# Sheet2.net
KiCad netlist of a schematic drawn in Altium Designer
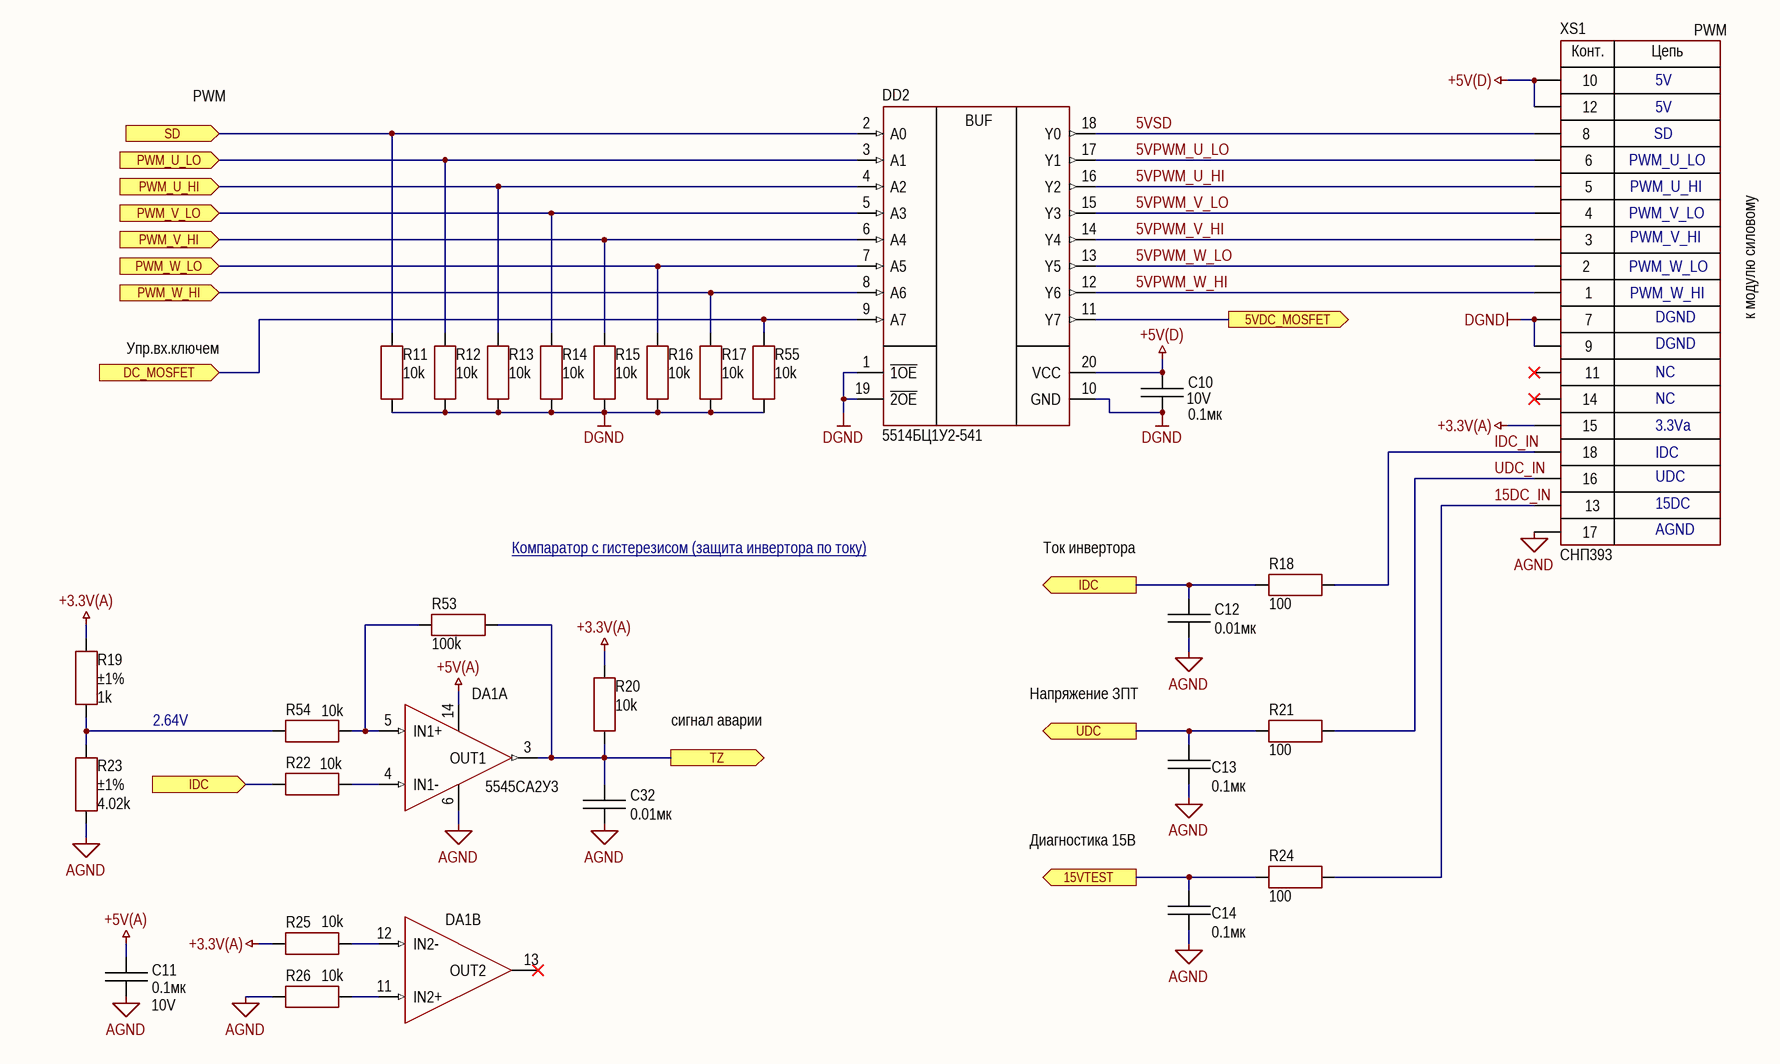
[diagram p0: Sheet2.SchDoc]

(export (version "E")
  (design (tool "Eeschema 10.0.6"))
  (components
    (comp (ref "C10")
      (value "0.1мк")
      (footprint "StandardCase:CAP: 0603P")
      (fields
        (field (name "MANUFACTURER") "Гириконд")
        (field (name "PARTNUMBER") "К10-79-10В-0,1 мкФ +80-20% H90")
        (field (name "VALUEMANUFACTURERPARTNUMBER") "Ceramic capacitor, 0.1мк, H90, +80-20%, 10V, 0603, -55...+125°C")
        (field (name "VOLTAGE") "10V")
      )
      (libsource (lib "Capacitor") (part "Ceramic_0603"))
    )
    (comp (ref "C11")
      (value "0.1мк")
      (footprint "StandardCase:CAP: 0603P")
      (fields
        (field (name "MANUFACTURER") "Гириконд")
        (field (name "PARTNUMBER") "К10-79-10В-0,1 мкФ +80-20% H90")
        (field (name "VALUEMANUFACTURERPARTNUMBER") "Ceramic capacitor, 0.1мк, H90, +80-20%, 10V, 0603, -55...+125°C")
        (field (name "VOLTAGE") "10V")
      )
      (libsource (lib "Capacitor") (part "Ceramic_0603"))
    )
    (comp (ref "C12")
      (value "0.01мк")
      (footprint "StandardCase:CAP: 0603P")
      (fields
        (field (name "MANUFACTURER") "Монолит")
        (field (name "PARTNUMBER") "К10-84в-1608М-50В-0.01мк ±20%-Н20-N-A")
        (field (name "VALUEMANUFACTURERPARTNUMBER") "Ceramic capacitor, 0.01мк, H20, ±20%, 50V, 0603, -55...+125°C")
      )
      (libsource (lib "Capacitor") (part "Ceramic_0603"))
    )
    (comp (ref "C13")
      (value "0.1мк")
      (footprint "StandardCase:CAP: 0603P")
      (fields
        (field (name "MANUFACTURER") "Гириконд")
        (field (name "PARTNUMBER") "К10-79-10В-0,1 мкФ +80-20% H90")
        (field (name "VALUEMANUFACTURERPARTNUMBER") "Ceramic capacitor, 0.1мк, H90, +80-20%, 10V, 0603, -55...+125°C")
      )
      (libsource (lib "Capacitor") (part "Ceramic_0603"))
    )
    (comp (ref "C14")
      (value "0.1мк")
      (footprint "StandardCase:CAP: 0603P")
      (fields
        (field (name "MANUFACTURER") "Гириконд")
        (field (name "PARTNUMBER") "К10-79-10В-0,1 мкФ +80-20% H90")
        (field (name "VALUEMANUFACTURERPARTNUMBER") "Ceramic capacitor, 0.1мк, H90, +80-20%, 10V, 0603, -55...+125°C")
      )
      (libsource (lib "Capacitor") (part "Ceramic_0603"))
    )
    (comp (ref "C32")
      (value "0.01мк")
      (footprint "StandardCase:CAP: 0603P")
      (fields
        (field (name "MANUFACTURER") "Монолит")
        (field (name "PARTNUMBER") "К10-84в-1608М-50В-0.01мк ±20%-Н20-N-A")
        (field (name "VALUEMANUFACTURERPARTNUMBER") "Ceramic capacitor, 0.01мк, H20, ±20%, 50V, 0603, -55...+125°C")
      )
      (libsource (lib "Capacitor") (part "Ceramic_0603"))
    )
    (comp (ref "DA1")
      (value "~")
      (footprint "StandardCase:16-Н04.16-1B")
      (description "Comparator USSR")
      (fields
        (field (name "MANUFACTURER") "НПП ВОСТОК")
        (field (name "VALUEMANUFACTURERPARTNUMBER") "IC comparator, Open Drain, от ± 1,5В до ± 16,5В, -60...+125°C, Н04.16-1В")
        (field (name "PARTNUMBER") "5545СА2У3")
      )
      (libsource (lib "IC. Comparator") (part "5545СА2У3"))
    )
    (comp (ref "DD2")
      (value "~")
      (footprint "StandardCase:20-QLCC (5121.20-A)")
      (description "USSR Buffer QFN")
      (fields
        (field (name "MANUFACTURER") "Анстрем")
        (field (name "VALUEMANUFACTURERPARTNUMBER") "8 канальный буфер, 4.5..5.5V, -60...+125°C, 5121.20-A")
        (field (name "PARTNUMBER") "5514БЦ1У2-541")
      )
      (libsource (lib "IC. Logic") (part "5514БЦ1У2-541"))
    )
    (comp (ref "R11")
      (value "10k")
      (footprint "RES: 0603P")
      (fields
        (field (name "MANUFACTURER") "ОАО Ресурс")
        (field (name "PARTNUMBER") "Р1-12-0,1ум.-10~кОм ±5%-М ШКАБ.434110.002 ТУ")
        (field (name "VALUEMANUFACTURERPARTNUMBER") "Resistor film, 10k, ±5%, 0603, 0.1W, -55...+125°C")
      )
      (libsource (lib "") (part "Resistor_0603_1"))
    )
    (comp (ref "R12")
      (value "10k")
      (footprint "RES: 0603P")
      (fields
        (field (name "MANUFACTURER") "ОАО Ресурс")
        (field (name "PARTNUMBER") "Р1-12-0,1ум.-10~кОм ±5%-М ШКАБ.434110.002 ТУ")
        (field (name "VALUEMANUFACTURERPARTNUMBER") "Resistor film, 10k, ±5%, 0603, 0.1W, -55...+125°C")
      )
      (libsource (lib "") (part "Resistor_0603_1"))
    )
    (comp (ref "R13")
      (value "10k")
      (footprint "RES: 0603P")
      (fields
        (field (name "MANUFACTURER") "ОАО Ресурс")
        (field (name "PARTNUMBER") "Р1-12-0,1ум.-10~кОм ±5%-М ШКАБ.434110.002 ТУ")
        (field (name "VALUEMANUFACTURERPARTNUMBER") "Resistor film, 10k, ±5%, 0603, 0.1W, -55...+125°C")
      )
      (libsource (lib "") (part "Resistor_0603_1"))
    )
    (comp (ref "R14")
      (value "10k")
      (footprint "RES: 0603P")
      (fields
        (field (name "MANUFACTURER") "ОАО Ресурс")
        (field (name "PARTNUMBER") "Р1-12-0,1ум.-10~кОм ±5%-М ШКАБ.434110.002 ТУ")
        (field (name "VALUEMANUFACTURERPARTNUMBER") "Resistor film, 10k, ±5%, 0603, 0.1W, -55...+125°C")
      )
      (libsource (lib "") (part "Resistor_0603_1"))
    )
    (comp (ref "R15")
      (value "10k")
      (footprint "RES: 0603P")
      (fields
        (field (name "MANUFACTURER") "ОАО Ресурс")
        (field (name "PARTNUMBER") "Р1-12-0,1ум.-10~кОм ±5%-М ШКАБ.434110.002 ТУ")
        (field (name "VALUEMANUFACTURERPARTNUMBER") "Resistor film, 10k, ±5%, 0603, 0.1W, -55...+125°C")
      )
      (libsource (lib "") (part "Resistor_0603_1"))
    )
    (comp (ref "R16")
      (value "10k")
      (footprint "RES: 0603P")
      (fields
        (field (name "MANUFACTURER") "ОАО Ресурс")
        (field (name "PARTNUMBER") "Р1-12-0,1ум.-10~кОм ±5%-М ШКАБ.434110.002 ТУ")
        (field (name "VALUEMANUFACTURERPARTNUMBER") "Resistor film, 10k, ±5%, 0603, 0.1W, -55...+125°C")
      )
      (libsource (lib "") (part "Resistor_0603_1"))
    )
    (comp (ref "R17")
      (value "10k")
      (footprint "RES: 0603P")
      (fields
        (field (name "MANUFACTURER") "ОАО Ресурс")
        (field (name "PARTNUMBER") "Р1-12-0,1ум.-10~кОм ±5%-М ШКАБ.434110.002 ТУ")
        (field (name "VALUEMANUFACTURERPARTNUMBER") "Resistor film, 10k, ±5%, 0603, 0.1W, -55...+125°C")
      )
      (libsource (lib "") (part "Resistor_0603_1"))
    )
    (comp (ref "R18")
      (value "100")
      (footprint "RES: 0603P")
      (fields
        (field (name "MANUFACTURER") "ОАО Ресурс")
        (field (name "PARTNUMBER") "Р1-12-0,1ум.-100~Ом ±5%-М ШКАБ.434110.002 ТУ")
        (field (name "VALUEMANUFACTURERPARTNUMBER") "Resistor film, 100, ±5%, 0603, 0.1W, -55...+125°C")
      )
      (libsource (lib "") (part "Resistor_0603_1"))
    )
    (comp (ref "R19")
      (value "1k")
      (footprint "RES: 0603P")
      (fields
        (field (name "MANUFACTURER") "ОАО Ресурс")
        (field (name "PARTNUMBER") "Р1-12-0,1ум.-1~кОм ±1%-М ШКАБ.434110.002 ТУ")
        (field (name "VALUEMANUFACTURERPARTNUMBER") "Resistor film, 1k, ±1%, 0603, 0.1W, -55...+125°C")
        (field (name "TOLERANCE") "±1%")
      )
      (libsource (lib "Resistor") (part "Resistor_0603"))
    )
    (comp (ref "R20")
      (value "10k")
      (footprint "RES: 0603P")
      (fields
        (field (name "MANUFACTURER") "ОАО Ресурс")
        (field (name "PARTNUMBER") "Р1-12-0,1ум.-10~кОм ±5%-М ШКАБ.434110.002 ТУ")
        (field (name "VALUEMANUFACTURERPARTNUMBER") "Resistor film, 10k, ±5%, 0603, 0.1W, -55...+125°C")
      )
      (libsource (lib "Resistor") (part "Resistor_0603"))
    )
    (comp (ref "R21")
      (value "100")
      (footprint "RES: 0603P")
      (fields
        (field (name "MANUFACTURER") "ОАО Ресурс")
        (field (name "PARTNUMBER") "Р1-12-0,1ум.-100~Ом ±5%-М ШКАБ.434110.002 ТУ")
        (field (name "VALUEMANUFACTURERPARTNUMBER") "Resistor film, 100, ±5%, 0603, 0.1W, -55...+125°C")
      )
      (libsource (lib "") (part "Resistor_0603_1"))
    )
    (comp (ref "R22")
      (value "10k")
      (footprint "RES: 0603P")
      (fields
        (field (name "MANUFACTURER") "ОАО Ресурс")
        (field (name "PARTNUMBER") "Р1-12-0,1ум.-10~кОм ±5%-М ШКАБ.434110.002 ТУ")
        (field (name "VALUEMANUFACTURERPARTNUMBER") "Resistor film, 10k, ±5%, 0603, 0.1W, -55...+125°C")
      )
      (libsource (lib "") (part "Resistor_0603_2"))
    )
    (comp (ref "R23")
      (value "4.02k")
      (footprint "RES: 0603P")
      (fields
        (field (name "MANUFACTURER") "ОАО Ресурс")
        (field (name "PARTNUMBER") "Р1-12-0,1ум.-4.02~кОм ±1%-М ШКАБ.434110.002 ТУ")
        (field (name "VALUEMANUFACTURERPARTNUMBER") "Resistor film, 4.02k, ±1%, 0603, 0.1W, -55...+125°C")
        (field (name "TOLERANCE") "±1%")
      )
      (libsource (lib "Resistor") (part "Resistor_0603"))
    )
    (comp (ref "R24")
      (value "100")
      (footprint "RES: 0603P")
      (fields
        (field (name "MANUFACTURER") "ОАО Ресурс")
        (field (name "PARTNUMBER") "Р1-12-0,1ум.-100~Ом ±5%-М ШКАБ.434110.002 ТУ")
        (field (name "VALUEMANUFACTURERPARTNUMBER") "Resistor film, 100, ±5%, 0603, 0.1W, -55...+125°C")
      )
      (libsource (lib "") (part "Resistor_0603_1"))
    )
    (comp (ref "R25")
      (value "10k")
      (footprint "RES: 0603P")
      (fields
        (field (name "MANUFACTURER") "ОАО Ресурс")
        (field (name "PARTNUMBER") "Р1-12-0,1ум.-10~кОм ±5%-М ШКАБ.434110.002 ТУ")
        (field (name "VALUEMANUFACTURERPARTNUMBER") "Resistor film, 10k, ±5%, 0603, 0.1W, -55...+125°C")
      )
      (libsource (lib "") (part "Resistor_0603_1"))
    )
    (comp (ref "R26")
      (value "10k")
      (footprint "RES: 0603P")
      (fields
        (field (name "MANUFACTURER") "ОАО Ресурс")
        (field (name "PARTNUMBER") "Р1-12-0,1ум.-10~кОм ±5%-М ШКАБ.434110.002 ТУ")
        (field (name "VALUEMANUFACTURERPARTNUMBER") "Resistor film, 10k, ±5%, 0603, 0.1W, -55...+125°C")
      )
      (libsource (lib "") (part "Resistor_0603_1"))
    )
    (comp (ref "R53")
      (value "100k")
      (footprint "RES: 0603P")
      (fields
        (field (name "MANUFACTURER") "ОАО Ресурс")
        (field (name "PARTNUMBER") "Р1-12-0,1ум.-100~кОм ±5%-М ШКАБ.434110.002 ТУ")
        (field (name "VALUEMANUFACTURERPARTNUMBER") "Resistor film, 100k, ±5%, 0603, 0.1W, -55...+125°C")
      )
      (libsource (lib "") (part "Resistor_0603_3"))
    )
    (comp (ref "R54")
      (value "10k")
      (footprint "RES: 0603P")
      (fields
        (field (name "MANUFACTURER") "ОАО Ресурс")
        (field (name "PARTNUMBER") "Р1-12-0,1ум.-10~кОм ±5%-М ШКАБ.434110.002 ТУ")
        (field (name "VALUEMANUFACTURERPARTNUMBER") "Resistor film, 10k, ±5%, 0603, 0.1W, -55...+125°C")
      )
      (libsource (lib "") (part "Resistor_0603_2"))
    )
    (comp (ref "R55")
      (value "10k")
      (footprint "RES: 0603P")
      (fields
        (field (name "MANUFACTURER") "ОАО Ресурс")
        (field (name "PARTNUMBER") "Р1-12-0,1ум.-10~кОм ±5%-М ШКАБ.434110.002 ТУ")
        (field (name "VALUEMANUFACTURERPARTNUMBER") "Resistor film, 10k, ±5%, 0603, 0.1W, -55...+125°C")
      )
      (libsource (lib "") (part "Resistor_0603_1"))
    )
    (comp (ref "XS1")
      (value "~")
      (footprint "CustomCase:CON: PBD-18")
      (fields
        (field (name "MANUFACTURER") "Электродеталь")
        (field (name "VALUEMANUFACTURERPARTNUMBER") "Connector, 18pin, 2.54mm, 500VAC, 3A")
        (field (name "PARTNUMBER") "СНП393-18РП21-2 РЮМК.430420.035 ТУ")
        (field (name "COMMENTTEXT") "СНП393")
      )
      (libsource (lib "Connector") (part "PBD-18"))
    )
  )
  (nets
    (net (code "1") (name "+3.3V(A)") (class "Default")
      (node (ref "R19") (pin "1") (pinfunction "1_1") (pintype "passive"))
      (node (ref "R20") (pin "1") (pinfunction "1_1") (pintype "passive"))
      (node (ref "R25") (pin "2") (pinfunction "2_2") (pintype "passive"))
      (node (ref "XS1") (pin "15") (pinfunction "15_15") (pintype "passive"))
    )
    (net (code "2") (name "+5V(A)") (class "Default")
      (node (ref "C11") (pin "2") (pinfunction "2_2") (pintype "power_in"))
      (node (ref "DA1") (pin "14") (pinfunction "V+_14") (pintype "power_in"))
    )
    (net (code "3") (name "+5V(D)") (class "Default")
      (node (ref "C10") (pin "2") (pinfunction "2_2") (pintype "power_in"))
      (node (ref "DD2") (pin "20") (pinfunction "VCC_20") (pintype "power_in"))
      (node (ref "XS1") (pin "10") (pinfunction "10_10") (pintype "passive"))
      (node (ref "XS1") (pin "12") (pinfunction "12_12") (pintype "passive"))
    )
    (net (code "4") (name "/5VDC_MOSFET") (class "Default")
      (node (ref "DD2") (pin "11") (pinfunction "Y7_11") (pintype "output"))
    )
    (net (code "5") (name "/5VPWM_U_HI") (class "Default")
      (node (ref "DD2") (pin "16") (pinfunction "Y2_16") (pintype "output"))
      (node (ref "XS1") (pin "5") (pinfunction "5_5") (pintype "passive"))
    )
    (net (code "6") (name "/5VPWM_U_LO") (class "Default")
      (node (ref "DD2") (pin "17") (pinfunction "Y1_17") (pintype "output"))
      (node (ref "XS1") (pin "6") (pinfunction "6_6") (pintype "passive"))
    )
    (net (code "7") (name "/5VPWM_V_HI") (class "Default")
      (node (ref "DD2") (pin "14") (pinfunction "Y4_14") (pintype "output"))
      (node (ref "XS1") (pin "3") (pinfunction "3_3") (pintype "passive"))
    )
    (net (code "8") (name "/5VPWM_V_LO") (class "Default")
      (node (ref "DD2") (pin "15") (pinfunction "Y3_15") (pintype "output"))
      (node (ref "XS1") (pin "4") (pinfunction "4_4") (pintype "passive"))
    )
    (net (code "9") (name "/5VPWM_W_HI") (class "Default")
      (node (ref "DD2") (pin "12") (pinfunction "Y6_12") (pintype "output"))
      (node (ref "XS1") (pin "1") (pinfunction "1_1") (pintype "passive"))
    )
    (net (code "10") (name "/5VPWM_W_LO") (class "Default")
      (node (ref "DD2") (pin "13") (pinfunction "Y5_13") (pintype "output"))
      (node (ref "XS1") (pin "2") (pinfunction "2_2") (pintype "passive"))
    )
    (net (code "11") (name "/5VSD") (class "Default")
      (node (ref "DD2") (pin "18") (pinfunction "Y0_18") (pintype "output"))
      (node (ref "XS1") (pin "8") (pinfunction "8_8") (pintype "passive"))
    )
    (net (code "12") (name "/15DC_IN") (class "Default")
      (node (ref "R24") (pin "1") (pinfunction "1_1") (pintype "passive"))
      (node (ref "XS1") (pin "13") (pinfunction "13_13") (pintype "passive"))
    )
    (net (code "13") (name "/15VTEST") (class "Default")
      (node (ref "C14") (pin "2") (pinfunction "2_2") (pintype "power_in"))
      (node (ref "R24") (pin "2") (pinfunction "2_2") (pintype "passive"))
    )
    (net (code "14") (name "/DC_MOSFET") (class "Default")
      (node (ref "DD2") (pin "9") (pinfunction "A7_9") (pintype "input"))
      (node (ref "R55") (pin "1") (pinfunction "1_1") (pintype "passive"))
    )
    (net (code "15") (name "/IDC") (class "Default")
      (node (ref "C12") (pin "1") (pinfunction "1_1") (pintype "passive"))
      (node (ref "R18") (pin "2") (pinfunction "2_2") (pintype "passive"))
      (node (ref "R22") (pin "1") (pinfunction "1_1") (pintype "passive"))
    )
    (net (code "16") (name "/IDC_IN") (class "Default")
      (node (ref "R18") (pin "1") (pinfunction "1_1") (pintype "passive"))
      (node (ref "XS1") (pin "18") (pinfunction "18_18") (pintype "passive"))
    )
    (net (code "17") (name "/PWM_U_HI") (class "Default")
      (node (ref "DD2") (pin "4") (pinfunction "A2_4") (pintype "input"))
      (node (ref "R13") (pin "1") (pinfunction "1_1") (pintype "passive"))
    )
    (net (code "18") (name "/PWM_U_LO") (class "Default")
      (node (ref "DD2") (pin "3") (pinfunction "A1_3") (pintype "input"))
      (node (ref "R12") (pin "1") (pinfunction "1_1") (pintype "passive"))
    )
    (net (code "19") (name "/PWM_V_HI") (class "Default")
      (node (ref "DD2") (pin "6") (pinfunction "A4_6") (pintype "input"))
      (node (ref "R15") (pin "1") (pinfunction "1_1") (pintype "passive"))
    )
    (net (code "20") (name "/PWM_V_LO") (class "Default")
      (node (ref "DD2") (pin "5") (pinfunction "A3_5") (pintype "input"))
      (node (ref "R14") (pin "1") (pinfunction "1_1") (pintype "passive"))
    )
    (net (code "21") (name "/PWM_W_HI") (class "Default")
      (node (ref "DD2") (pin "8") (pinfunction "A6_8") (pintype "input"))
      (node (ref "R17") (pin "1") (pinfunction "1_1") (pintype "passive"))
    )
    (net (code "22") (name "/PWM_W_LO") (class "Default")
      (node (ref "DD2") (pin "7") (pinfunction "A5_7") (pintype "input"))
      (node (ref "R16") (pin "1") (pinfunction "1_1") (pintype "passive"))
    )
    (net (code "23") (name "/SD") (class "Default")
      (node (ref "DD2") (pin "2") (pinfunction "A0_2") (pintype "input"))
      (node (ref "R11") (pin "1") (pinfunction "1_1") (pintype "passive"))
    )
    (net (code "24") (name "/TZ") (class "Default")
      (node (ref "C32") (pin "1") (pinfunction "1_1") (pintype "passive"))
      (node (ref "DA1") (pin "3") (pinfunction "OUT1_3") (pintype "power_in"))
      (node (ref "R20") (pin "2") (pinfunction "2_2") (pintype "passive"))
      (node (ref "R53") (pin "2") (pinfunction "2_2") (pintype "passive"))
    )
    (net (code "25") (name "/UDC") (class "Default")
      (node (ref "C13") (pin "2") (pinfunction "2_2") (pintype "power_in"))
      (node (ref "R21") (pin "2") (pinfunction "2_2") (pintype "passive"))
    )
    (net (code "26") (name "/UDC_IN") (class "Default")
      (node (ref "R21") (pin "1") (pinfunction "1_1") (pintype "passive"))
      (node (ref "XS1") (pin "16") (pinfunction "16_16") (pintype "passive"))
    )
    (net (code "27") (name "AGND") (class "Default")
      (node (ref "C11") (pin "1") (pinfunction "1_1") (pintype "passive"))
      (node (ref "C12") (pin "2") (pinfunction "2_2") (pintype "power_in"))
      (node (ref "C13") (pin "1") (pinfunction "1_1") (pintype "passive"))
      (node (ref "C14") (pin "1") (pinfunction "1_1") (pintype "passive"))
      (node (ref "C32") (pin "2") (pinfunction "2_2") (pintype "power_in"))
      (node (ref "DA1") (pin "6") (pinfunction "V-_6") (pintype "power_in"))
      (node (ref "R23") (pin "2") (pinfunction "2_2") (pintype "passive"))
      (node (ref "R26") (pin "2") (pinfunction "2_2") (pintype "passive"))
      (node (ref "XS1") (pin "17") (pinfunction "17_17") (pintype "passive"))
    )
    (net (code "28") (name "DGND") (class "Default")
      (node (ref "C10") (pin "1") (pinfunction "1_1") (pintype "passive"))
      (node (ref "DD2") (pin "1") (pinfunction "~{1OE}_1") (pintype "passive"))
      (node (ref "DD2") (pin "10") (pinfunction "GND_10") (pintype "power_in"))
      (node (ref "DD2") (pin "19") (pinfunction "~{2OE}_19") (pintype "passive"))
      (node (ref "R11") (pin "2") (pinfunction "2_2") (pintype "passive"))
      (node (ref "R12") (pin "2") (pinfunction "2_2") (pintype "passive"))
      (node (ref "R13") (pin "2") (pinfunction "2_2") (pintype "passive"))
      (node (ref "R14") (pin "2") (pinfunction "2_2") (pintype "passive"))
      (node (ref "R15") (pin "2") (pinfunction "2_2") (pintype "passive"))
      (node (ref "R16") (pin "2") (pinfunction "2_2") (pintype "passive"))
      (node (ref "R17") (pin "2") (pinfunction "2_2") (pintype "passive"))
      (node (ref "R55") (pin "2") (pinfunction "2_2") (pintype "passive"))
      (node (ref "XS1") (pin "7") (pinfunction "7_7") (pintype "passive"))
      (node (ref "XS1") (pin "9") (pinfunction "9_9") (pintype "passive"))
    )
    (net (code "29") (name "Net-(DA1A-IN1+)") (class "Default")
      (node (ref "DA1") (pin "5") (pinfunction "IN1+_5") (pintype "input"))
      (node (ref "R53") (pin "1") (pinfunction "1_1") (pintype "passive"))
      (node (ref "R54") (pin "2") (pinfunction "2_2") (pintype "passive"))
    )
    (net (code "30") (name "Net-(DA1A-IN1-)") (class "Default")
      (node (ref "DA1") (pin "4") (pinfunction "IN1-_4") (pintype "input"))
      (node (ref "R22") (pin "2") (pinfunction "2_2") (pintype "passive"))
    )
    (net (code "31") (name "Net-(DA1B-IN2+)") (class "Default")
      (node (ref "DA1") (pin "11") (pinfunction "IN2+_11") (pintype "input"))
      (node (ref "R26") (pin "1") (pinfunction "1_1") (pintype "passive"))
    )
    (net (code "32") (name "Net-(DA1B-IN2-)") (class "Default")
      (node (ref "DA1") (pin "12") (pinfunction "IN2-_12") (pintype "input"))
      (node (ref "R25") (pin "1") (pinfunction "1_1") (pintype "passive"))
    )
    (net (code "33") (name "Net-(R19-Pad2)") (class "Default")
      (node (ref "R19") (pin "2") (pinfunction "2_2") (pintype "passive"))
      (node (ref "R23") (pin "1") (pinfunction "1_1") (pintype "passive"))
      (node (ref "R54") (pin "1") (pinfunction "1_1") (pintype "passive"))
    )
    (net (code "34") (name "unconnected-(DA1B-OUT2-Pad13)") (class "Default")
      (node (ref "DA1") (pin "13") (pinfunction "OUT2_13") (pintype "power_in+no_connect"))
    )
    (net (code "35") (name "unconnected-(XS1-Pad11)") (class "Default")
      (node (ref "XS1") (pin "11") (pinfunction "11_11") (pintype "passive+no_connect"))
    )
    (net (code "36") (name "unconnected-(XS1-Pad14)") (class "Default")
      (node (ref "XS1") (pin "14") (pinfunction "14_14") (pintype "passive+no_connect"))
    )
  )
)
